# 03_mcu_switches.net
KiCad netlist of a schematic drawn in Altium Designer
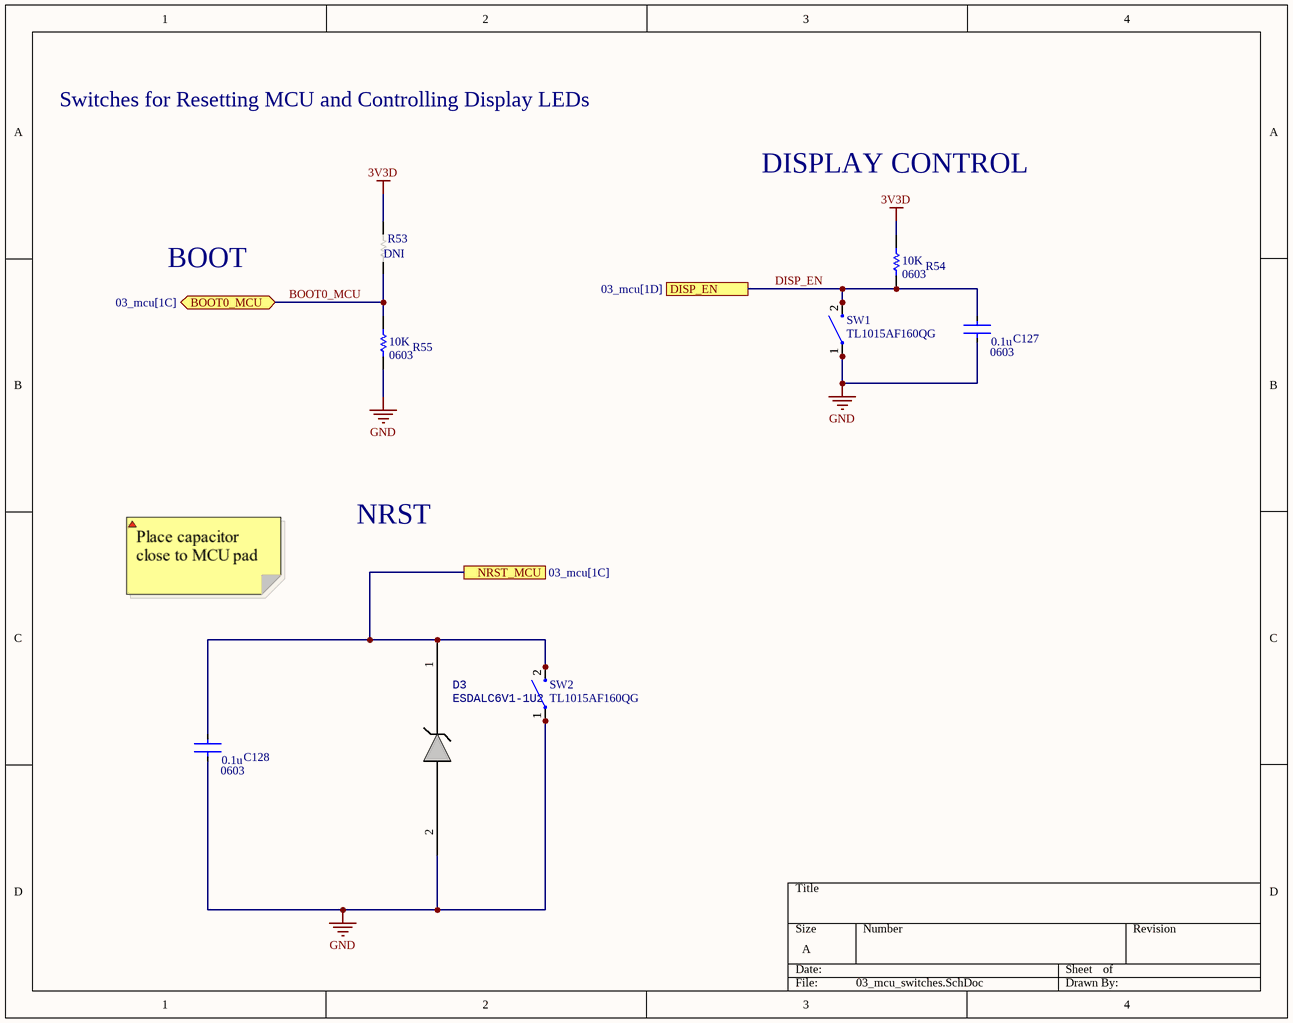
[diagram p0: 03_mcu_switches.SchDoc]

(export (version "E")
  (design (tool "Eeschema 10.0.6"))
  (components
    (comp (ref "C127")
      (value "CGA3E2X7R1H104K080AA")
      (footprint "CAPTDK0603")
      (description "CAP CER 0.1UF 50V X7R 0603")
      (libsource (lib "tcspc00") (part "CGA3E2X7R1H104K080AA"))
    )
    (comp (ref "C128")
      (value "CGA3E2X7R1H104K080AA")
      (footprint "CAPTDK0603")
      (description "CAP CER 0.1UF 50V X7R 0603")
      (libsource (lib "tcspc00") (part "CGA3E2X7R1H104K080AA"))
    )
    (comp (ref "D3")
      (value "ESDALC6V1-1U2")
      (footprint "DIODE_ESDALC6V1-1U2_STM")
      (description "TVS DIODE 3VWM ST0201")
      (libsource (lib "tcspc00") (part "ESDALC6V1"))
    )
    (comp (ref "R53")
      (value "DNI")
      (footprint "RES_0603")
      (description "RES DNI 0603")
      (libsource (lib "tcspc00") (part "R0603"))
    )
    (comp (ref "R54")
      (value "RMCF0603JG10K0")
      (footprint "RES-STACK-POLE-0603")
      (description "RES 10K OHM 5% 1/10W 0603")
      (libsource (lib "tcspc00") (part "RMCF0603JG10K0"))
    )
    (comp (ref "R55")
      (value "RMCF0603JG10K0")
      (footprint "RES-STACK-POLE-0603")
      (description "RES 10K OHM 5% 1/10W 0603")
      (libsource (lib "tcspc00") (part "RMCF0603JG10K0"))
    )
    (comp (ref "SW1")
      (value "TL1015AF160QG")
      (footprint "TACTILE-SWITCH")
      (description "SWITCH TACTILE SPST-NO 0.05A 12V")
      (libsource (lib "tcspc00") (part "TL1015AF160QG"))
    )
    (comp (ref "SW2")
      (value "TL1015AF160QG")
      (footprint "TACTILE-SWITCH")
      (description "SWITCH TACTILE SPST-NO 0.05A 12V")
      (libsource (lib "tcspc00") (part "TL1015AF160QG"))
    )
  )
  (nets
    (net (code "2") (name "/BOOT0_MCU") (class "Default")
      (node (ref "R53") (pin "1") (pinfunction "1_1") (pintype "passive"))
      (node (ref "R55") (pin "2") (pinfunction "2_2") (pintype "passive"))
    )
    (net (code "3") (name "/DISP_EN") (class "Default")
      (node (ref "C127") (pin "1") (pinfunction "1_1") (pintype "passive"))
      (node (ref "R54") (pin "1") (pinfunction "1_1") (pintype "passive"))
      (node (ref "SW1") (pin "2") (pinfunction "2_2") (pintype "passive"))
    )
    (net (code "4") (name "/NRST_MCU") (class "Default")
      (node (ref "C128") (pin "1") (pinfunction "1_1") (pintype "passive"))
      (node (ref "D3") (pin "1") (pinfunction "1_1") (pintype "passive"))
      (node (ref "SW2") (pin "2") (pinfunction "2_2") (pintype "passive"))
    )
    (net (code "5") (name "3V3D") (class "Default")
      (node (ref "R53") (pin "2") (pinfunction "2_2") (pintype "passive"))
      (node (ref "R54") (pin "2") (pinfunction "2_2") (pintype "passive"))
    )
    (net (code "6") (name "GND") (class "Default")
      (node (ref "C127") (pin "2") (pinfunction "2_2") (pintype "passive"))
      (node (ref "C128") (pin "2") (pinfunction "2_2") (pintype "passive"))
      (node (ref "D3") (pin "2") (pinfunction "2_2") (pintype "passive"))
      (node (ref "R55") (pin "1") (pinfunction "1_1") (pintype "passive"))
      (node (ref "SW1") (pin "1") (pinfunction "1_1") (pintype "passive"))
      (node (ref "SW2") (pin "1") (pinfunction "1_1") (pintype "passive"))
    )
  )
)
